# powersafe2.net
KiCad netlist of a schematic drawn in EAGLE
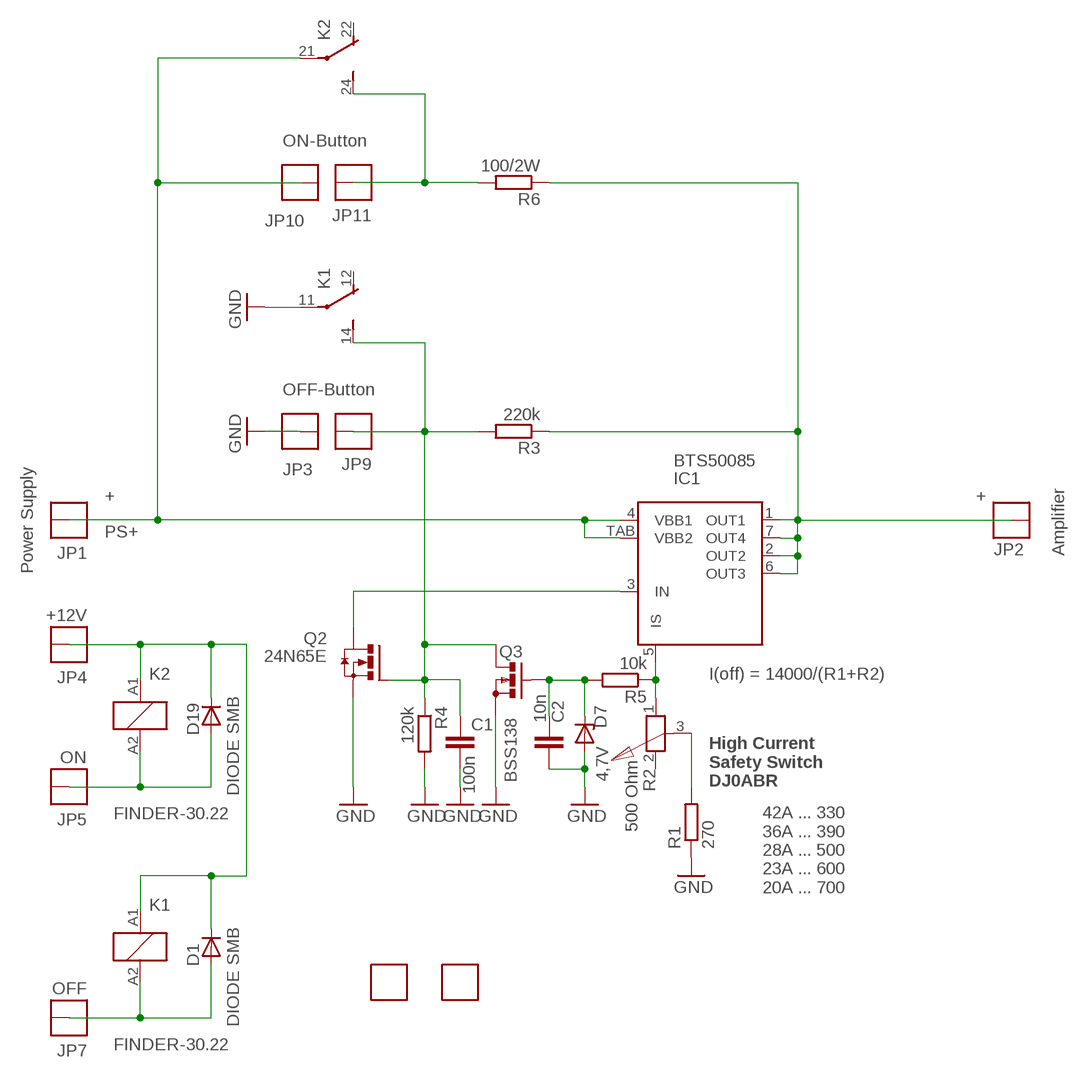
[diagram p0: schematic, sheet 1]

(export (version "E")
  (design (tool "Eeschema 10.0.6"))
  (components
    (comp (ref "C1")
      (value "100n")
      (footprint "eagle-import:C0603K")
      (libsource (lib "eagle-import") (part "C-EUC0603K"))
    )
    (comp (ref "C2")
      (value "10n")
      (footprint "eagle-import:C0603K")
      (libsource (lib "eagle-import") (part "C-EUC0603K"))
    )
    (comp (ref "D1")
      (value "DIODE SMB")
      (footprint "eagle-import:SMB")
      (libsource (lib "eagle-import") (part "DIODE-SMB"))
    )
    (comp (ref "D7")
      (value "4,7V")
      (footprint "eagle-import:SMA")
      (libsource (lib "eagle-import") (part "ZPYSMA"))
    )
    (comp (ref "D19")
      (value "DIODE SMB")
      (footprint "eagle-import:SMB")
      (libsource (lib "eagle-import") (part "DIODE-SMB"))
    )
    (comp (ref "FID1")
      (value "FIDUCIAL")
      (footprint "eagle-import:FIDUCIAL")
      (libsource (lib "eagle-import") (part "FIDUCIAL"))
    )
    (comp (ref "FID2")
      (value "FIDUCIAL")
      (footprint "eagle-import:FIDUCIAL")
      (libsource (lib "eagle-import") (part "FIDUCIAL"))
    )
    (comp (ref "IC1")
      (value "BTS50085")
      (footprint "eagle-import:PG-TO220-7-4")
      (libsource (lib "eagle-import") (part "BTS50085"))
    )
    (comp (ref "JP1")
      (value "THICKPINPIN_4QMM")
      (footprint "eagle-import:PIN_4QMM")
      (libsource (lib "eagle-import") (part "THICKPINPIN_4QMM"))
    )
    (comp (ref "JP2")
      (value "THICKPINPIN_4QMM")
      (footprint "eagle-import:PIN_4QMM")
      (libsource (lib "eagle-import") (part "THICKPINPIN_4QMM"))
    )
    (comp (ref "JP3")
      (value "THICKPINSQUARE")
      (footprint "eagle-import:THICKPIN")
      (libsource (lib "eagle-import") (part "THICKPINSQUARE"))
    )
    (comp (ref "JP4")
      (value "+12V")
      (footprint "eagle-import:THICKPIN_OCT")
      (libsource (lib "eagle-import") (part "THICKPINOCT"))
    )
    (comp (ref "JP5")
      (value "ON")
      (footprint "eagle-import:THICKPIN_OCT")
      (libsource (lib "eagle-import") (part "THICKPINOCT"))
    )
    (comp (ref "JP7")
      (value "OFF")
      (footprint "eagle-import:THICKPIN_OCT")
      (libsource (lib "eagle-import") (part "THICKPINOCT"))
    )
    (comp (ref "JP9")
      (value "THICKPINSQUARE")
      (footprint "eagle-import:THICKPIN")
      (libsource (lib "eagle-import") (part "THICKPINSQUARE"))
    )
    (comp (ref "JP10")
      (value "THICKPINSQUARE")
      (footprint "eagle-import:THICKPIN")
      (libsource (lib "eagle-import") (part "THICKPINSQUARE"))
    )
    (comp (ref "JP11")
      (value "THICKPINSQUARE")
      (footprint "eagle-import:THICKPIN")
      (libsource (lib "eagle-import") (part "THICKPINSQUARE"))
    )
    (comp (ref "K1")
      (value "FINDER-30.22")
      (footprint "eagle-import:FINDER-30.22")
      (libsource (lib "eagle-import") (part "FINDER-30.22"))
    )
    (comp (ref "K2")
      (value "FINDER-30.22")
      (footprint "eagle-import:FINDER-30.22")
      (libsource (lib "eagle-import") (part "FINDER-30.22"))
    )
    (comp (ref "Q2")
      (value "24N65E")
      (footprint "eagle-import:D2PACK")
      (libsource (lib "eagle-import") (part "IRF3704S"))
    )
    (comp (ref "Q3")
      (value "BSS138")
      (footprint "eagle-import:SOT23")
      (libsource (lib "eagle-import") (part "BS170_SMD"))
    )
    (comp (ref "R1")
      (value "270")
      (footprint "eagle-import:R0603")
      (libsource (lib "eagle-import") (part "R-EU_R0603"))
    )
    (comp (ref "R2")
      (value "500 Ohm")
      (footprint "eagle-import:MINIPOTI")
      (libsource (lib "eagle-import") (part "MINIPOTI-S"))
    )
    (comp (ref "R3")
      (value "220k")
      (footprint "eagle-import:R0603")
      (libsource (lib "eagle-import") (part "R-EU_R0603"))
    )
    (comp (ref "R4")
      (value "120k")
      (footprint "eagle-import:R0603")
      (libsource (lib "eagle-import") (part "R-EU_R0603"))
    )
    (comp (ref "R5")
      (value "10k")
      (footprint "eagle-import:R0603")
      (libsource (lib "eagle-import") (part "R-EU_R0603"))
    )
    (comp (ref "R6")
      (value "100/2W")
      (footprint "eagle-import:P0613_15")
      (libsource (lib "eagle-import") (part "R-EU_0613/15"))
    )
  )
  (nets
    (net (code "1") (name "/PS+") (class "Default")
      (node (ref "IC1") (pin "4") (pinfunction "VBB1_4") (pintype "bidirectional"))
      (node (ref "IC1") (pin "TAB") (pinfunction "VBB2_TAB") (pintype "bidirectional"))
      (node (ref "JP1") (pin "P$1") (pinfunction "1_P$1") (pintype "bidirectional"))
      (node (ref "JP10") (pin "1") (pinfunction "1_1") (pintype "bidirectional"))
      (node (ref "K2") (pin "21") (pinfunction "P_21") (pintype "passive"))
    )
    (net (code "2") (name "GND") (class "Default")
      (node (ref "C1") (pin "2") (pinfunction "2_2") (pintype "passive"))
      (node (ref "C2") (pin "2") (pinfunction "2_2") (pintype "passive"))
      (node (ref "D7") (pin "A") (pinfunction "A_A") (pintype "passive"))
      (node (ref "JP3") (pin "1") (pinfunction "1_1") (pintype "bidirectional"))
      (node (ref "K1") (pin "11") (pinfunction "P_11") (pintype "passive"))
      (node (ref "Q2") (pin "3") (pinfunction "S_3") (pintype "passive"))
      (node (ref "Q3") (pin "2") (pinfunction "S_2") (pintype "passive"))
      (node (ref "R1") (pin "1") (pinfunction "1_1") (pintype "passive"))
      (node (ref "R4") (pin "2") (pinfunction "2_2") (pintype "passive"))
    )
    (net (code "3") (name "Net-(IC1-IN)") (class "Default")
      (node (ref "IC1") (pin "3") (pinfunction "IN_3") (pintype "bidirectional"))
      (node (ref "Q2") (pin "2") (pinfunction "D_2") (pintype "passive"))
    )
    (net (code "4") (name "Net-(IC1-IS)") (class "Default")
      (node (ref "IC1") (pin "5") (pinfunction "IS_5") (pintype "bidirectional"))
      (node (ref "R2") (pin "1") (pinfunction "1_1") (pintype "passive"))
      (node (ref "R5") (pin "1") (pinfunction "1_1") (pintype "passive"))
    )
    (net (code "5") (name "Net-(IC1-OUT1)") (class "Default")
      (node (ref "IC1") (pin "1") (pinfunction "OUT1_1") (pintype "bidirectional"))
      (node (ref "IC1") (pin "2") (pinfunction "OUT2_2") (pintype "bidirectional"))
      (node (ref "IC1") (pin "6") (pinfunction "OUT3_6") (pintype "bidirectional"))
      (node (ref "IC1") (pin "7") (pinfunction "OUT4_7") (pintype "bidirectional"))
      (node (ref "JP2") (pin "P$1") (pinfunction "1_P$1") (pintype "bidirectional"))
      (node (ref "R3") (pin "1") (pinfunction "1_1") (pintype "passive"))
      (node (ref "R6") (pin "1") (pinfunction "1_1") (pintype "passive"))
    )
    (net (code "6") (name "Net-(K1A-S)") (class "Default")
      (node (ref "C1") (pin "1") (pinfunction "1_1") (pintype "passive"))
      (node (ref "JP9") (pin "1") (pinfunction "1_1") (pintype "bidirectional"))
      (node (ref "K1") (pin "14") (pinfunction "S_14") (pintype "passive"))
      (node (ref "Q2") (pin "1") (pinfunction "G_1") (pintype "passive"))
      (node (ref "Q3") (pin "3") (pinfunction "D_3") (pintype "passive"))
      (node (ref "R3") (pin "2") (pinfunction "2_2") (pintype "passive"))
      (node (ref "R4") (pin "1") (pinfunction "1_1") (pintype "passive"))
    )
    (net (code "7") (name "Net-(K1C-1)") (class "Default")
      (node (ref "D1") (pin "C") (pinfunction "C_C") (pintype "passive"))
      (node (ref "D19") (pin "C") (pinfunction "C_C") (pintype "passive"))
      (node (ref "JP4") (pin "1") (pinfunction "1_1") (pintype "bidirectional"))
      (node (ref "K1") (pin "A1") (pinfunction "1_A1") (pintype "passive"))
      (node (ref "K2") (pin "A1") (pinfunction "1_A1") (pintype "passive"))
    )
    (net (code "8") (name "Net-(K1C-2)") (class "Default")
      (node (ref "D1") (pin "A") (pinfunction "A_A") (pintype "passive"))
      (node (ref "JP7") (pin "1") (pinfunction "1_1") (pintype "bidirectional"))
      (node (ref "K1") (pin "A2") (pinfunction "2_A2") (pintype "passive"))
    )
    (net (code "9") (name "Net-(K2B-S)") (class "Default")
      (node (ref "JP11") (pin "1") (pinfunction "1_1") (pintype "bidirectional"))
      (node (ref "K2") (pin "24") (pinfunction "S_24") (pintype "passive"))
      (node (ref "R6") (pin "2") (pinfunction "2_2") (pintype "passive"))
    )
    (net (code "10") (name "Net-(K2C-2)") (class "Default")
      (node (ref "D19") (pin "A") (pinfunction "A_A") (pintype "passive"))
      (node (ref "JP5") (pin "1") (pinfunction "1_1") (pintype "bidirectional"))
      (node (ref "K2") (pin "A2") (pinfunction "2_A2") (pintype "passive"))
    )
    (net (code "11") (name "Net-(Q3-G)") (class "Default")
      (node (ref "C2") (pin "1") (pinfunction "1_1") (pintype "passive"))
      (node (ref "D7") (pin "C") (pinfunction "C_C") (pintype "passive"))
      (node (ref "Q3") (pin "1") (pinfunction "G_1") (pintype "passive"))
      (node (ref "R5") (pin "2") (pinfunction "2_2") (pintype "passive"))
    )
    (net (code "12") (name "Net-(R1-Pad2)") (class "Default")
      (node (ref "R1") (pin "2") (pinfunction "2_2") (pintype "passive"))
      (node (ref "R2") (pin "3") (pinfunction "3_3") (pintype "passive"))
    )
    (net (code "13") (name "unconnected-(FID1-PadP$1)") (class "Default")
      (node (ref "FID1") (pin "P$1") (pinfunction "P$1_P$1") (pintype "bidirectional"))
    )
    (net (code "14") (name "unconnected-(FID2-PadP$1)") (class "Default")
      (node (ref "FID2") (pin "P$1") (pinfunction "P$1_P$1") (pintype "bidirectional"))
    )
    (net (code "15") (name "unconnected-(K1A-O-Pad12)") (class "Default")
      (node (ref "K1") (pin "12") (pinfunction "O_12") (pintype "passive"))
    )
    (net (code "16") (name "unconnected-(K2B-O-Pad22)") (class "Default")
      (node (ref "K2") (pin "22") (pinfunction "O_22") (pintype "passive"))
    )
    (net (code "17") (name "unconnected-(R2-Pad2)") (class "Default")
      (node (ref "R2") (pin "2") (pinfunction "2_2") (pintype "passive"))
    )
  )
)
